# 1.net
KiCad netlist of a schematic drawn in EAGLE
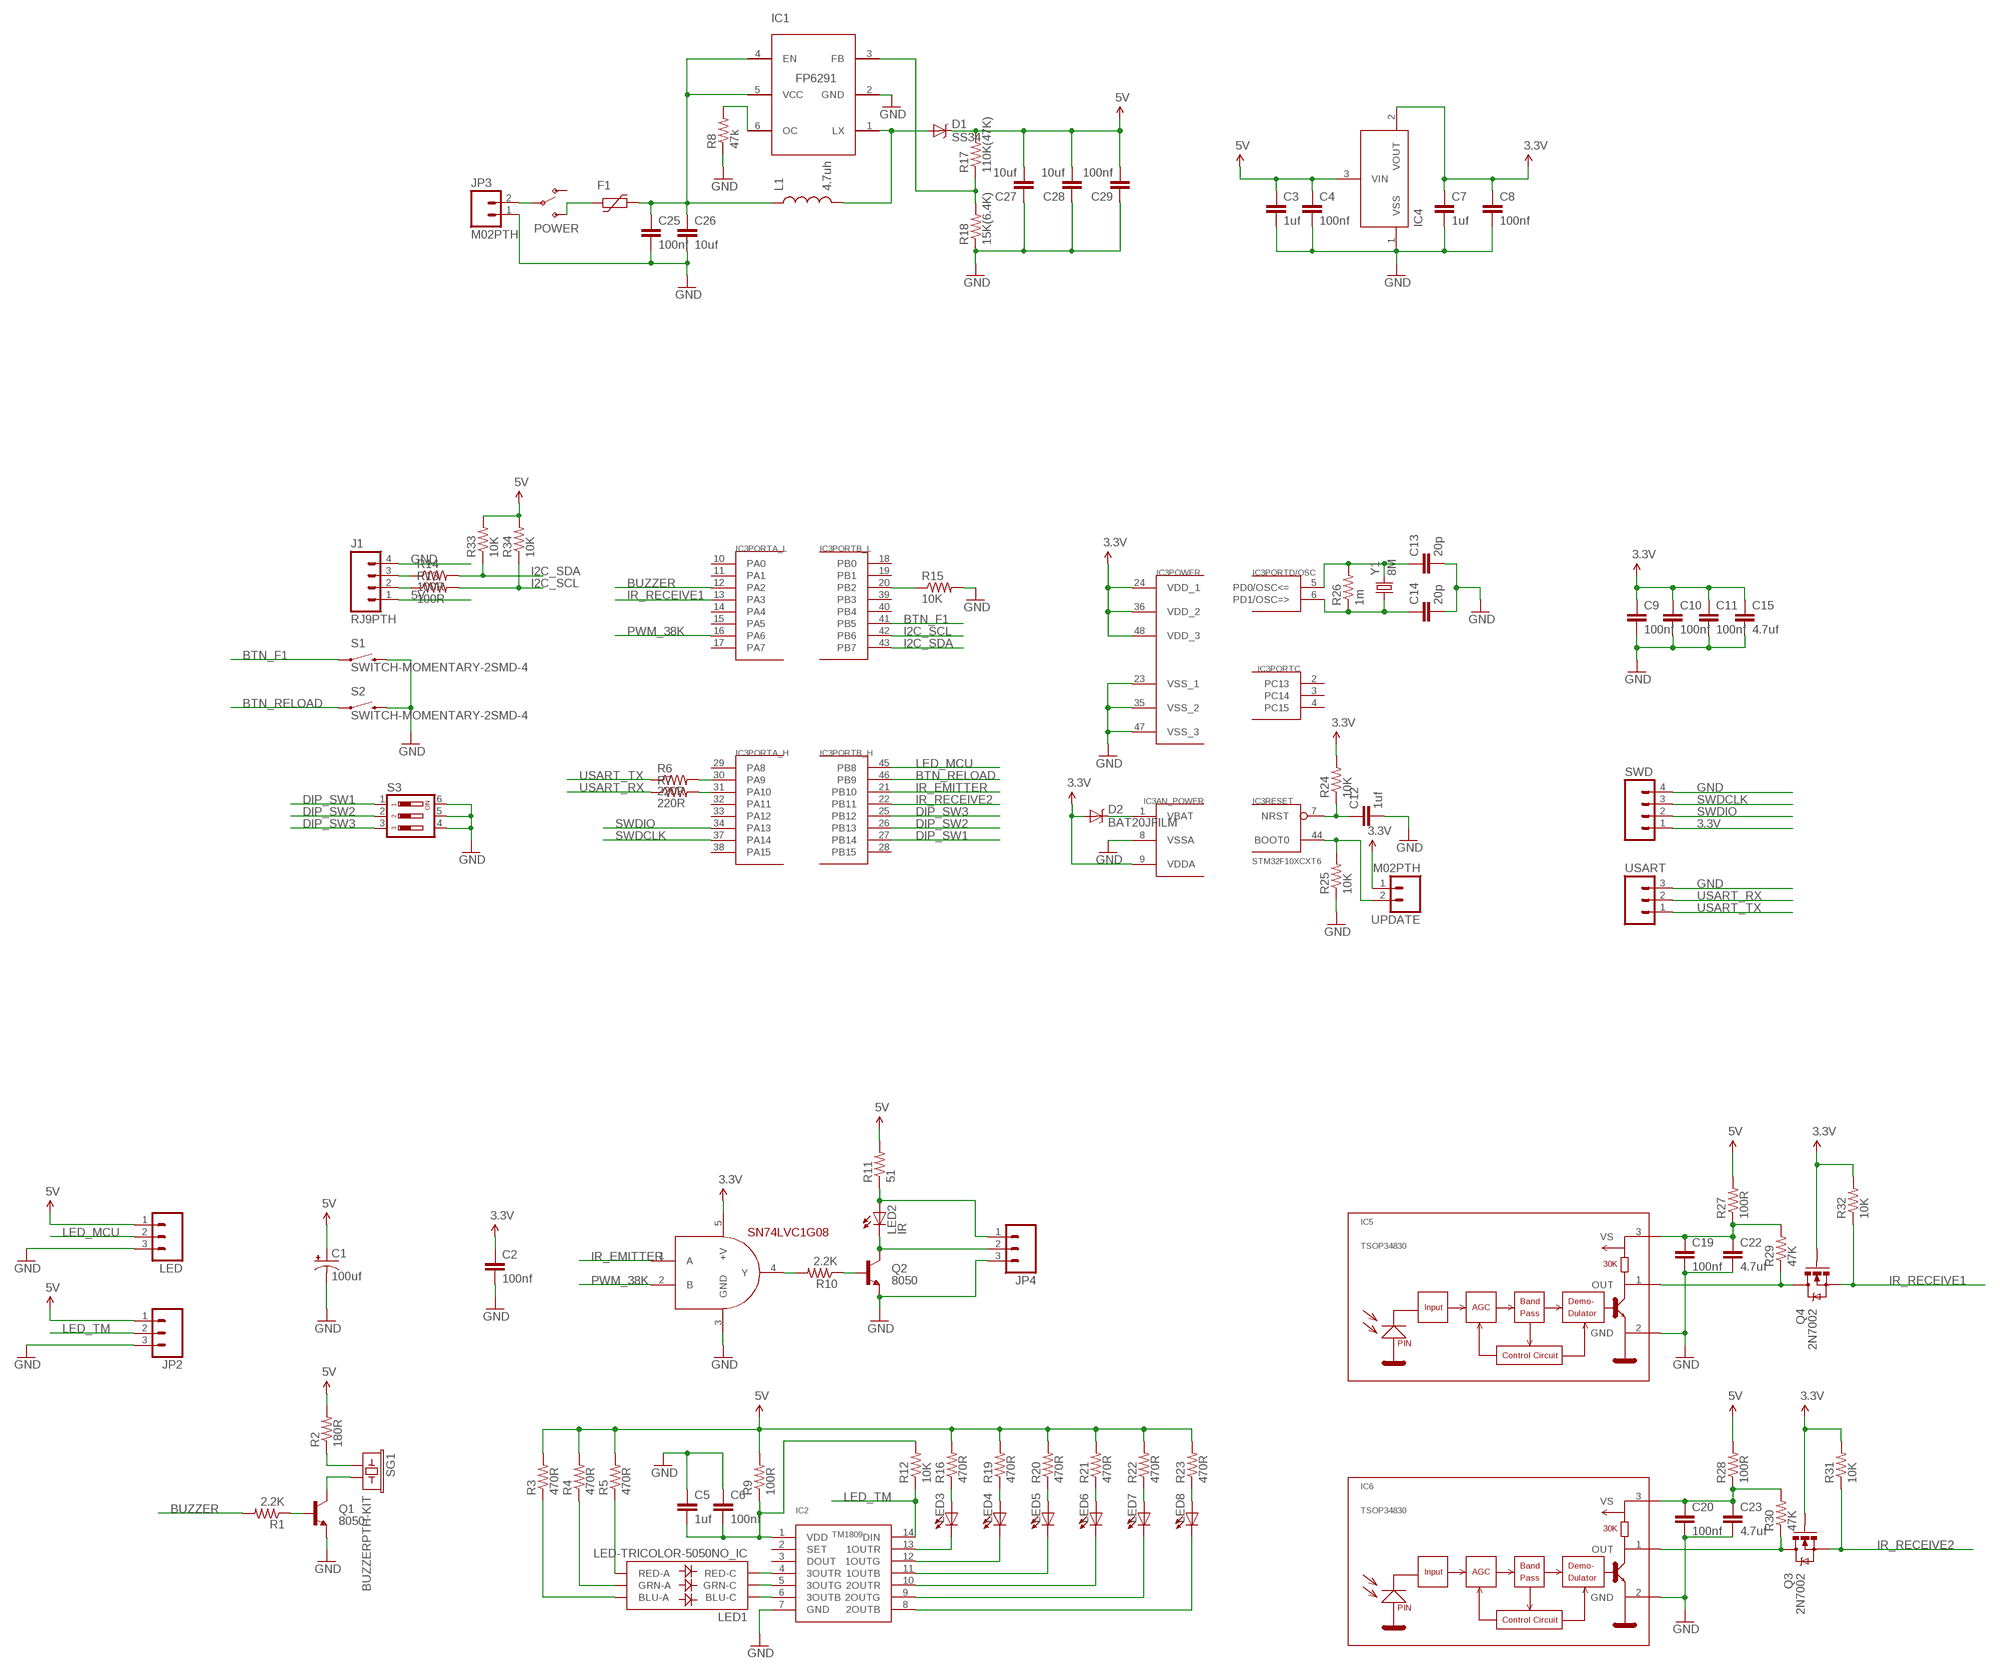
[diagram p0: schematic, sheet 1]

(export (version "E")
  (design (tool "Eeschema 10.0.6"))
  (components
    (comp (ref "C1")
      (value "100uf")
      (footprint "eagle-import:EIA6032")
      (libsource (lib "eagle-import") (part "CAP_POL6032"))
    )
    (comp (ref "C2")
      (value "100nf")
      (footprint "eagle-import:0603-CAP")
      (libsource (lib "eagle-import") (part "CAP0603-CAP"))
    )
    (comp (ref "C3")
      (value "1uf")
      (footprint "eagle-import:0603-CAP")
      (libsource (lib "eagle-import") (part "CAP0603-CAP"))
    )
    (comp (ref "C4")
      (value "100nf")
      (footprint "eagle-import:0603-CAP")
      (libsource (lib "eagle-import") (part "CAP0603-CAP"))
    )
    (comp (ref "C5")
      (value "1uf")
      (footprint "eagle-import:0603-CAP")
      (libsource (lib "eagle-import") (part "CAP0603-CAP"))
    )
    (comp (ref "C6")
      (value "100nf")
      (footprint "eagle-import:0603-CAP")
      (libsource (lib "eagle-import") (part "CAP0603-CAP"))
    )
    (comp (ref "C7")
      (value "1uf")
      (footprint "eagle-import:0603-CAP")
      (libsource (lib "eagle-import") (part "CAP0603-CAP"))
    )
    (comp (ref "C8")
      (value "100nf")
      (footprint "eagle-import:0603-CAP")
      (libsource (lib "eagle-import") (part "CAP0603-CAP"))
    )
    (comp (ref "C9")
      (value "100nf")
      (footprint "eagle-import:0603-CAP")
      (libsource (lib "eagle-import") (part "CAP0603-CAP"))
    )
    (comp (ref "C10")
      (value "100nf")
      (footprint "eagle-import:0603-CAP")
      (libsource (lib "eagle-import") (part "CAP0603-CAP"))
    )
    (comp (ref "C11")
      (value "100nf")
      (footprint "eagle-import:0603-CAP")
      (libsource (lib "eagle-import") (part "CAP0603-CAP"))
    )
    (comp (ref "C12")
      (value "1uf")
      (footprint "eagle-import:0603-CAP")
      (libsource (lib "eagle-import") (part "CAP0603-CAP"))
    )
    (comp (ref "C13")
      (value "20p")
      (footprint "eagle-import:0603-CAP")
      (libsource (lib "eagle-import") (part "CAP0603-CAP"))
    )
    (comp (ref "C14")
      (value "20p")
      (footprint "eagle-import:0603-CAP")
      (libsource (lib "eagle-import") (part "CAP0603-CAP"))
    )
    (comp (ref "C15")
      (value "4.7uf")
      (footprint "eagle-import:0603-CAP")
      (libsource (lib "eagle-import") (part "CAP0603-CAP"))
    )
    (comp (ref "C19")
      (value "100nf")
      (footprint "eagle-import:0603-CAP")
      (libsource (lib "eagle-import") (part "CAP0603-CAP"))
    )
    (comp (ref "C20")
      (value "100nf")
      (footprint "eagle-import:0603-CAP")
      (libsource (lib "eagle-import") (part "CAP0603-CAP"))
    )
    (comp (ref "C22")
      (value "4.7uf")
      (footprint "eagle-import:0603-CAP")
      (libsource (lib "eagle-import") (part "CAP0603-CAP"))
    )
    (comp (ref "C23")
      (value "4.7uf")
      (footprint "eagle-import:0603-CAP")
      (libsource (lib "eagle-import") (part "CAP0603-CAP"))
    )
    (comp (ref "C25")
      (value "100nf")
      (footprint "eagle-import:0603-CAP")
      (libsource (lib "eagle-import") (part "CAP0603-CAP"))
    )
    (comp (ref "C26")
      (value "10uf")
      (footprint "eagle-import:0603-CAP")
      (libsource (lib "eagle-import") (part "CAP0603-CAP"))
    )
    (comp (ref "C27")
      (value "10uf")
      (footprint "eagle-import:0603-CAP")
      (libsource (lib "eagle-import") (part "CAP0603-CAP"))
    )
    (comp (ref "C28")
      (value "10uf")
      (footprint "eagle-import:0603-CAP")
      (libsource (lib "eagle-import") (part "CAP0603-CAP"))
    )
    (comp (ref "C29")
      (value "100nf")
      (footprint "eagle-import:0603-CAP")
      (libsource (lib "eagle-import") (part "CAP0603-CAP"))
    )
    (comp (ref "D1")
      (value "SS34")
      (footprint "eagle-import:SMA-DIODE")
      (libsource (lib "eagle-import") (part "DIODE-SCHOTTKY_"))
    )
    (comp (ref "D2")
      (value "BAT20JFILM")
      (footprint "eagle-import:SOD-323")
      (libsource (lib "eagle-import") (part "BAT20JFILM"))
    )
    (comp (ref "F1")
      (value "PTC-FUSE")
      (footprint "eagle-import:R0805")
      (libsource (lib "eagle-import") (part "PTC-FUSE"))
    )
    (comp (ref "IC1")
      (value "FP6291")
      (footprint "eagle-import:SOT23-6")
      (libsource (lib "eagle-import") (part "FP6291"))
    )
    (comp (ref "IC2")
      (value "TM1809")
      (footprint "eagle-import:SOP-14")
      (libsource (lib "eagle-import") (part "TM1809"))
    )
    (comp (ref "IC3")
      (value "STM32F10XCXT6")
      (footprint "eagle-import:TQFP48")
      (libsource (lib "eagle-import") (part "STM32F10XCXT6"))
    )
    (comp (ref "IC4")
      (value "XC6206")
      (footprint "eagle-import:SOT23-3")
      (libsource (lib "eagle-import") (part "XC6206"))
    )
    (comp (ref "IC5")
      (value "TSOP34830")
      (footprint "eagle-import:TSOP348")
      (libsource (lib "eagle-import") (part "TSOP34830"))
    )
    (comp (ref "IC6")
      (value "TSOP34830")
      (footprint "eagle-import:TSOP348")
      (libsource (lib "eagle-import") (part "TSOP34830"))
    )
    (comp (ref "J1")
      (value "RJ9PTH")
      (footprint "eagle-import:RJ9")
      (libsource (lib "eagle-import") (part "RJ9PTH"))
    )
    (comp (ref "JP2")
      (value "M03PTH")
      (footprint "eagle-import:1X03")
      (libsource (lib "eagle-import") (part "M03PTH"))
    )
    (comp (ref "JP3")
      (value "M02PTH")
      (footprint "eagle-import:1X02")
      (libsource (lib "eagle-import") (part "M02PTH"))
    )
    (comp (ref "JP4")
      (value "M03PTH")
      (footprint "eagle-import:1X03")
      (libsource (lib "eagle-import") (part "M03PTH"))
    )
    (comp (ref "L1")
      (value "4.7uh")
      (footprint "eagle-import:CR75_V2")
      (libsource (lib "eagle-import") (part "INDUCTORCR75_V2"))
    )
    (comp (ref "LED")
      (value "M03PTH")
      (footprint "eagle-import:1X03")
      (libsource (lib "eagle-import") (part "M03PTH"))
    )
    (comp (ref "LED1")
      (value "LED-TRICOLOR-5050NO_IC")
      (footprint "eagle-import:LED-TRICOLOR-5050")
      (libsource (lib "eagle-import") (part "LED-TRICOLOR-5050NO_IC"))
    )
    (comp (ref "LED2")
      (value "IR")
      (footprint "eagle-import:LED5MM")
      (libsource (lib "eagle-import") (part "LED5MM"))
    )
    (comp (ref "LED3")
      (value "LED0805")
      (footprint "eagle-import:CHIPLED_0805")
      (libsource (lib "eagle-import") (part "LED0805"))
    )
    (comp (ref "LED4")
      (value "LED0805")
      (footprint "eagle-import:CHIPLED_0805")
      (libsource (lib "eagle-import") (part "LED0805"))
    )
    (comp (ref "LED5")
      (value "LED0805")
      (footprint "eagle-import:CHIPLED_0805")
      (libsource (lib "eagle-import") (part "LED0805"))
    )
    (comp (ref "LED6")
      (value "LED0805")
      (footprint "eagle-import:CHIPLED_0805")
      (libsource (lib "eagle-import") (part "LED0805"))
    )
    (comp (ref "LED7")
      (value "LED0805")
      (footprint "eagle-import:CHIPLED_0805")
      (libsource (lib "eagle-import") (part "LED0805"))
    )
    (comp (ref "LED8")
      (value "LED0805")
      (footprint "eagle-import:CHIPLED_0805")
      (libsource (lib "eagle-import") (part "LED0805"))
    )
    (comp (ref "POWER")
      (value "SWITCH-SPST3AM6")
      (footprint "eagle-import:SWITCH-SPDT-AM#6")
      (libsource (lib "eagle-import") (part "SWITCH-SPST3AM6"))
    )
    (comp (ref "Q1")
      (value "8050")
      (footprint "eagle-import:SOT23")
      (libsource (lib "eagle-import") (part "TRANSISTOR_NPNSOT23"))
    )
    (comp (ref "Q2")
      (value "8050")
      (footprint "eagle-import:SOT23")
      (libsource (lib "eagle-import") (part "TRANSISTOR_NPNSOT23"))
    )
    (comp (ref "Q3")
      (value "2N7002")
      (footprint "eagle-import:SOT23")
      (libsource (lib "eagle-import") (part "MOSFET-NCHANNELBSS138"))
    )
    (comp (ref "Q4")
      (value "2N7002")
      (footprint "eagle-import:SOT23")
      (libsource (lib "eagle-import") (part "MOSFET-NCHANNELBSS138"))
    )
    (comp (ref "R1")
      (value "2.2K")
      (footprint "eagle-import:0603-RES")
      (libsource (lib "eagle-import") (part "RESISTOR0603-RES"))
    )
    (comp (ref "R2")
      (value "180R")
      (footprint "eagle-import:0603-RES")
      (libsource (lib "eagle-import") (part "RESISTOR0603-RES"))
    )
    (comp (ref "R3")
      (value "470R")
      (footprint "eagle-import:0603-RES")
      (libsource (lib "eagle-import") (part "RESISTOR0603-RES"))
    )
    (comp (ref "R4")
      (value "470R")
      (footprint "eagle-import:0603-RES")
      (libsource (lib "eagle-import") (part "RESISTOR0603-RES"))
    )
    (comp (ref "R5")
      (value "470R")
      (footprint "eagle-import:0603-RES")
      (libsource (lib "eagle-import") (part "RESISTOR0603-RES"))
    )
    (comp (ref "R6")
      (value "220R")
      (footprint "eagle-import:0603-RES")
      (libsource (lib "eagle-import") (part "RESISTOR0603-RES"))
    )
    (comp (ref "R7")
      (value "220R")
      (footprint "eagle-import:0603-RES")
      (libsource (lib "eagle-import") (part "RESISTOR0603-RES"))
    )
    (comp (ref "R8")
      (value "47k")
      (footprint "eagle-import:0603-RES")
      (libsource (lib "eagle-import") (part "RESISTOR0603-RES"))
    )
    (comp (ref "R9")
      (value "100R")
      (footprint "eagle-import:0603-RES")
      (libsource (lib "eagle-import") (part "RESISTOR0603-RES"))
    )
    (comp (ref "R10")
      (value "2.2K")
      (footprint "eagle-import:0603-RES")
      (libsource (lib "eagle-import") (part "RESISTOR0603-RES"))
    )
    (comp (ref "R11")
      (value "51")
      (footprint "eagle-import:1206")
      (libsource (lib "eagle-import") (part "SparkFun-Resistors_RESISTOR1206"))
    )
    (comp (ref "R12")
      (value "10K")
      (footprint "eagle-import:0603-RES")
      (libsource (lib "eagle-import") (part "RESISTOR0603-RES"))
    )
    (comp (ref "R13")
      (value "100R")
      (footprint "eagle-import:0603-RES")
      (libsource (lib "eagle-import") (part "RESISTOR0603-RES"))
    )
    (comp (ref "R14")
      (value "100R")
      (footprint "eagle-import:0603-RES")
      (libsource (lib "eagle-import") (part "RESISTOR0603-RES"))
    )
    (comp (ref "R15")
      (value "10K")
      (footprint "eagle-import:0603-RES")
      (libsource (lib "eagle-import") (part "RESISTOR0603-RES"))
    )
    (comp (ref "R16")
      (value "470R")
      (footprint "eagle-import:0603-RES")
      (libsource (lib "eagle-import") (part "RESISTOR0603-RES"))
    )
    (comp (ref "R17")
      (value "110K(47K)")
      (footprint "eagle-import:0603-RES")
      (libsource (lib "eagle-import") (part "RESISTOR0603-RES"))
    )
    (comp (ref "R18")
      (value "15K(6.4K)")
      (footprint "eagle-import:0603-RES")
      (libsource (lib "eagle-import") (part "RESISTOR0603-RES"))
    )
    (comp (ref "R19")
      (value "470R")
      (footprint "eagle-import:0603-RES")
      (libsource (lib "eagle-import") (part "RESISTOR0603-RES"))
    )
    (comp (ref "R20")
      (value "470R")
      (footprint "eagle-import:0603-RES")
      (libsource (lib "eagle-import") (part "RESISTOR0603-RES"))
    )
    (comp (ref "R21")
      (value "470R")
      (footprint "eagle-import:0603-RES")
      (libsource (lib "eagle-import") (part "RESISTOR0603-RES"))
    )
    (comp (ref "R22")
      (value "470R")
      (footprint "eagle-import:0603-RES")
      (libsource (lib "eagle-import") (part "RESISTOR0603-RES"))
    )
    (comp (ref "R23")
      (value "470R")
      (footprint "eagle-import:0603-RES")
      (libsource (lib "eagle-import") (part "RESISTOR0603-RES"))
    )
    (comp (ref "R24")
      (value "10K")
      (footprint "eagle-import:0603-RES")
      (libsource (lib "eagle-import") (part "RESISTOR0603-RES"))
    )
    (comp (ref "R25")
      (value "10K")
      (footprint "eagle-import:0603-RES")
      (libsource (lib "eagle-import") (part "RESISTOR0603-RES"))
    )
    (comp (ref "R26")
      (value "1m")
      (footprint "eagle-import:0603-RES")
      (libsource (lib "eagle-import") (part "RESISTOR0603-RES"))
    )
    (comp (ref "R27")
      (value "100R")
      (footprint "eagle-import:0603-RES")
      (libsource (lib "eagle-import") (part "RESISTOR0603-RES"))
    )
    (comp (ref "R28")
      (value "100R")
      (footprint "eagle-import:0603-RES")
      (libsource (lib "eagle-import") (part "RESISTOR0603-RES"))
    )
    (comp (ref "R29")
      (value "47K")
      (footprint "eagle-import:0603-RES")
      (libsource (lib "eagle-import") (part "RESISTOR0603-RES"))
    )
    (comp (ref "R30")
      (value "47K")
      (footprint "eagle-import:0603-RES")
      (libsource (lib "eagle-import") (part "RESISTOR0603-RES"))
    )
    (comp (ref "R31")
      (value "10K")
      (footprint "eagle-import:0603-RES")
      (libsource (lib "eagle-import") (part "RESISTOR0603-RES"))
    )
    (comp (ref "R32")
      (value "10K")
      (footprint "eagle-import:0603-RES")
      (libsource (lib "eagle-import") (part "RESISTOR0603-RES"))
    )
    (comp (ref "R33")
      (value "10K")
      (footprint "eagle-import:0603-RES")
      (libsource (lib "eagle-import") (part "RESISTOR0603-RES"))
    )
    (comp (ref "R34")
      (value "10K")
      (footprint "eagle-import:0603-RES")
      (libsource (lib "eagle-import") (part "RESISTOR0603-RES"))
    )
    (comp (ref "S1")
      (value "SWITCH-MOMENTARY-2SMD-4")
      (footprint "eagle-import:TACTILE_SWITCH_TALL")
      (libsource (lib "eagle-import") (part "SWITCH-MOMENTARY-2SMD-4"))
    )
    (comp (ref "S2")
      (value "SWITCH-MOMENTARY-2SMD-4")
      (footprint "eagle-import:TACTILE_SWITCH_TALL")
      (libsource (lib "eagle-import") (part "SWITCH-MOMENTARY-2SMD-4"))
    )
    (comp (ref "S3")
      (value "DIP03YL")
      (footprint "eagle-import:DIP03YL")
      (libsource (lib "eagle-import") (part "DIP03YL"))
    )
    (comp (ref "SG1")
      (value "BUZZERPTH-KIT")
      (footprint "eagle-import:BUZZER-12MM-KIT")
      (libsource (lib "eagle-import") (part "BUZZERPTH-KIT"))
    )
    (comp (ref "SWD")
      (value "M04PTH")
      (footprint "eagle-import:1X04")
      (libsource (lib "eagle-import") (part "M04PTH"))
    )
    (comp (ref "U$1")
      (value "SN74LVC1G08")
      (footprint "eagle-import:SOT23-5")
      (libsource (lib "eagle-import") (part "SN74LVC1G08"))
    )
    (comp (ref "UPDATE")
      (value "M02PTH")
      (footprint "eagle-import:1X02")
      (libsource (lib "eagle-import") (part "M02PTH"))
    )
    (comp (ref "USART")
      (value "M03PTH")
      (footprint "eagle-import:1X03")
      (libsource (lib "eagle-import") (part "M03PTH"))
    )
    (comp (ref "Y1")
      (value "8M")
      (footprint "eagle-import:CRYSTAL-TXC-7A")
      (libsource (lib "eagle-import") (part "CRYSTALTXC-7A"))
    )
  )
  (nets
    (net (code "1") (name "/BTN_F1") (class "Default")
      (node (ref "IC3") (pin "41") (pinfunction "PB5_41") (pintype "bidirectional"))
      (node (ref "S1") (pin "A2") (pinfunction "1_A2") (pintype "passive"))
    )
    (net (code "2") (name "/BTN_RELOAD") (class "Default")
      (node (ref "IC3") (pin "46") (pinfunction "PB9_46") (pintype "bidirectional"))
      (node (ref "S2") (pin "A2") (pinfunction "1_A2") (pintype "passive"))
    )
    (net (code "3") (name "/BUZZER") (class "Default")
      (node (ref "IC3") (pin "12") (pinfunction "PA2_12") (pintype "bidirectional"))
      (node (ref "R1") (pin "2") (pinfunction "2_2") (pintype "passive"))
    )
    (net (code "4") (name "/DIP_SW1") (class "Default")
      (node (ref "IC3") (pin "27") (pinfunction "PB14_27") (pintype "bidirectional"))
      (node (ref "S3") (pin "1") (pinfunction "1_1") (pintype "passive"))
    )
    (net (code "5") (name "/DIP_SW2") (class "Default")
      (node (ref "IC3") (pin "26") (pinfunction "PB13_26") (pintype "bidirectional"))
      (node (ref "S3") (pin "2") (pinfunction "2_2") (pintype "passive"))
    )
    (net (code "6") (name "/DIP_SW3") (class "Default")
      (node (ref "IC3") (pin "25") (pinfunction "PB12_25") (pintype "bidirectional"))
      (node (ref "S3") (pin "3") (pinfunction "3_3") (pintype "passive"))
    )
    (net (code "7") (name "/I2C_SCL") (class "Default")
      (node (ref "IC3") (pin "42") (pinfunction "PB6_42") (pintype "bidirectional"))
      (node (ref "R13") (pin "2") (pinfunction "2_2") (pintype "passive"))
      (node (ref "R34") (pin "1") (pinfunction "1_1") (pintype "passive"))
    )
    (net (code "8") (name "/I2C_SDA") (class "Default")
      (node (ref "IC3") (pin "43") (pinfunction "PB7_43") (pintype "bidirectional"))
      (node (ref "R14") (pin "2") (pinfunction "2_2") (pintype "passive"))
      (node (ref "R33") (pin "1") (pinfunction "1_1") (pintype "passive"))
    )
    (net (code "9") (name "/IR_EMITTER") (class "Default")
      (node (ref "IC3") (pin "21") (pinfunction "PB10_21") (pintype "bidirectional"))
      (node (ref "U$1") (pin "1") (pinfunction "A_1") (pintype "bidirectional"))
    )
    (net (code "10") (name "/IR_RECEIVE1") (class "Default")
      (node (ref "IC3") (pin "13") (pinfunction "PA3_13") (pintype "bidirectional"))
      (node (ref "Q4") (pin "2") (pinfunction "S_2") (pintype "passive"))
      (node (ref "R32") (pin "1") (pinfunction "1_1") (pintype "passive"))
    )
    (net (code "11") (name "/IR_RECEIVE2") (class "Default")
      (node (ref "IC3") (pin "22") (pinfunction "PB11_22") (pintype "bidirectional"))
      (node (ref "Q3") (pin "2") (pinfunction "S_2") (pintype "passive"))
      (node (ref "R31") (pin "1") (pinfunction "1_1") (pintype "passive"))
    )
    (net (code "12") (name "/LED_MCU") (class "Default")
      (node (ref "IC3") (pin "45") (pinfunction "PB8_45") (pintype "bidirectional"))
      (node (ref "LED") (pin "2") (pinfunction "2_2") (pintype "passive"))
    )
    (net (code "13") (name "/LED_TM") (class "Default")
      (node (ref "IC2") (pin "14") (pinfunction "DIN_14") (pintype "input"))
      (node (ref "JP2") (pin "2") (pinfunction "2_2") (pintype "passive"))
      (node (ref "R12") (pin "1") (pinfunction "1_1") (pintype "passive"))
    )
    (net (code "14") (name "/PWM_38K") (class "Default")
      (node (ref "IC3") (pin "16") (pinfunction "PA6_16") (pintype "bidirectional"))
      (node (ref "U$1") (pin "2") (pinfunction "B_2") (pintype "bidirectional"))
    )
    (net (code "15") (name "/SWDCLK") (class "Default")
      (node (ref "IC3") (pin "37") (pinfunction "PA14_37") (pintype "bidirectional"))
      (node (ref "SWD") (pin "3") (pinfunction "3_3") (pintype "passive"))
    )
    (net (code "16") (name "/SWDIO") (class "Default")
      (node (ref "IC3") (pin "34") (pinfunction "PA13_34") (pintype "bidirectional"))
      (node (ref "SWD") (pin "2") (pinfunction "2_2") (pintype "passive"))
    )
    (net (code "17") (name "/USART_RX") (class "Default")
      (node (ref "R7") (pin "1") (pinfunction "1_1") (pintype "passive"))
      (node (ref "USART") (pin "2") (pinfunction "2_2") (pintype "passive"))
    )
    (net (code "18") (name "/USART_TX") (class "Default")
      (node (ref "R6") (pin "1") (pinfunction "1_1") (pintype "passive"))
      (node (ref "USART") (pin "1") (pinfunction "1_1") (pintype "passive"))
    )
    (net (code "19") (name "3.3V") (class "Default")
      (node (ref "C10") (pin "1") (pinfunction "1_1") (pintype "passive"))
      (node (ref "C11") (pin "1") (pinfunction "1_1") (pintype "passive"))
      (node (ref "C15") (pin "1") (pinfunction "1_1") (pintype "passive"))
      (node (ref "C2") (pin "1") (pinfunction "1_1") (pintype "passive"))
      (node (ref "C7") (pin "1") (pinfunction "1_1") (pintype "passive"))
      (node (ref "C8") (pin "1") (pinfunction "1_1") (pintype "passive"))
      (node (ref "C9") (pin "1") (pinfunction "1_1") (pintype "passive"))
      (node (ref "D2") (pin "2") (pinfunction "A_2") (pintype "passive"))
      (node (ref "IC3") (pin "24") (pinfunction "VDD_1_24") (pintype "power_in"))
      (node (ref "IC3") (pin "36") (pinfunction "VDD_2_36") (pintype "power_in"))
      (node (ref "IC3") (pin "48") (pinfunction "VDD_3_48") (pintype "power_in"))
      (node (ref "IC3") (pin "9") (pinfunction "VDDA_9") (pintype "power_in"))
      (node (ref "IC4") (pin "2") (pinfunction "VOUT_2") (pintype "power_in"))
      (node (ref "Q3") (pin "1") (pinfunction "G_1") (pintype "passive"))
      (node (ref "Q4") (pin "1") (pinfunction "G_1") (pintype "passive"))
      (node (ref "R24") (pin "2") (pinfunction "2_2") (pintype "passive"))
      (node (ref "R31") (pin "2") (pinfunction "2_2") (pintype "passive"))
      (node (ref "R32") (pin "2") (pinfunction "2_2") (pintype "passive"))
      (node (ref "SWD") (pin "1") (pinfunction "1_1") (pintype "passive"))
      (node (ref "U$1") (pin "5") (pinfunction "+V_5") (pintype "bidirectional"))
      (node (ref "UPDATE") (pin "1") (pinfunction "1_1") (pintype "passive"))
    )
    (net (code "20") (name "5V") (class "Default")
      (node (ref "C1") (pin "P$1") (pinfunction "+_P$1") (pintype "passive"))
      (node (ref "C27") (pin "2") (pinfunction "2_2") (pintype "passive"))
      (node (ref "C28") (pin "2") (pinfunction "2_2") (pintype "passive"))
      (node (ref "C29") (pin "2") (pinfunction "2_2") (pintype "passive"))
      (node (ref "C3") (pin "1") (pinfunction "1_1") (pintype "passive"))
      (node (ref "C4") (pin "1") (pinfunction "1_1") (pintype "passive"))
      (node (ref "D1") (pin "C") (pinfunction "C_C") (pintype "passive"))
      (node (ref "IC4") (pin "3") (pinfunction "VIN_3") (pintype "power_in"))
      (node (ref "J1") (pin "1") (pinfunction "1_1") (pintype "passive"))
      (node (ref "JP2") (pin "1") (pinfunction "1_1") (pintype "passive"))
      (node (ref "LED") (pin "1") (pinfunction "1_1") (pintype "passive"))
      (node (ref "R11") (pin "2") (pinfunction "2_2") (pintype "passive"))
      (node (ref "R16") (pin "2") (pinfunction "2_2") (pintype "passive"))
      (node (ref "R17") (pin "2") (pinfunction "2_2") (pintype "passive"))
      (node (ref "R19") (pin "2") (pinfunction "2_2") (pintype "passive"))
      (node (ref "R2") (pin "2") (pinfunction "2_2") (pintype "passive"))
      (node (ref "R20") (pin "2") (pinfunction "2_2") (pintype "passive"))
      (node (ref "R21") (pin "2") (pinfunction "2_2") (pintype "passive"))
      (node (ref "R22") (pin "2") (pinfunction "2_2") (pintype "passive"))
      (node (ref "R23") (pin "2") (pinfunction "2_2") (pintype "passive"))
      (node (ref "R27") (pin "2") (pinfunction "2_2") (pintype "passive"))
      (node (ref "R28") (pin "2") (pinfunction "2_2") (pintype "passive"))
      (node (ref "R3") (pin "2") (pinfunction "2_2") (pintype "passive"))
      (node (ref "R33") (pin "2") (pinfunction "2_2") (pintype "passive"))
      (node (ref "R34") (pin "2") (pinfunction "2_2") (pintype "passive"))
      (node (ref "R4") (pin "2") (pinfunction "2_2") (pintype "passive"))
      (node (ref "R5") (pin "2") (pinfunction "2_2") (pintype "passive"))
      (node (ref "R9") (pin "2") (pinfunction "2_2") (pintype "passive"))
    )
    (net (code "21") (name "GND") (class "Default")
      (node (ref "C1") (pin "P$2") (pinfunction "-_P$2") (pintype "passive"))
      (node (ref "C10") (pin "2") (pinfunction "2_2") (pintype "passive"))
      (node (ref "C11") (pin "2") (pinfunction "2_2") (pintype "passive"))
      (node (ref "C12") (pin "2") (pinfunction "2_2") (pintype "passive"))
      (node (ref "C13") (pin "2") (pinfunction "2_2") (pintype "passive"))
      (node (ref "C14") (pin "2") (pinfunction "2_2") (pintype "passive"))
      (node (ref "C15") (pin "2") (pinfunction "2_2") (pintype "passive"))
      (node (ref "C19") (pin "2") (pinfunction "2_2") (pintype "passive"))
      (node (ref "C2") (pin "2") (pinfunction "2_2") (pintype "passive"))
      (node (ref "C20") (pin "2") (pinfunction "2_2") (pintype "passive"))
      (node (ref "C22") (pin "2") (pinfunction "2_2") (pintype "passive"))
      (node (ref "C23") (pin "2") (pinfunction "2_2") (pintype "passive"))
      (node (ref "C25") (pin "2") (pinfunction "2_2") (pintype "passive"))
      (node (ref "C26") (pin "2") (pinfunction "2_2") (pintype "passive"))
      (node (ref "C27") (pin "1") (pinfunction "1_1") (pintype "passive"))
      (node (ref "C28") (pin "1") (pinfunction "1_1") (pintype "passive"))
      (node (ref "C29") (pin "1") (pinfunction "1_1") (pintype "passive"))
      (node (ref "C3") (pin "2") (pinfunction "2_2") (pintype "passive"))
      (node (ref "C4") (pin "2") (pinfunction "2_2") (pintype "passive"))
      (node (ref "C5") (pin "1") (pinfunction "1_1") (pintype "passive"))
      (node (ref "C6") (pin "1") (pinfunction "1_1") (pintype "passive"))
      (node (ref "C7") (pin "2") (pinfunction "2_2") (pintype "passive"))
      (node (ref "C8") (pin "2") (pinfunction "2_2") (pintype "passive"))
      (node (ref "C9") (pin "2") (pinfunction "2_2") (pintype "passive"))
      (node (ref "IC1") (pin "2") (pinfunction "GND_2") (pintype "power_in"))
      (node (ref "IC2") (pin "7") (pinfunction "GND_7") (pintype "power_in"))
      (node (ref "IC3") (pin "23") (pinfunction "VSS_1_23") (pintype "power_in"))
      (node (ref "IC3") (pin "35") (pinfunction "VSS_2_35") (pintype "power_in"))
      (node (ref "IC3") (pin "47") (pinfunction "VSS_3_47") (pintype "power_in"))
      (node (ref "IC3") (pin "8") (pinfunction "VSSA_8") (pintype "power_in"))
      (node (ref "IC4") (pin "1") (pinfunction "VSS_1") (pintype "power_in"))
      (node (ref "IC5") (pin "2") (pinfunction "GND_2") (pintype "power_in"))
      (node (ref "IC6") (pin "2") (pinfunction "GND_2") (pintype "power_in"))
      (node (ref "J1") (pin "4") (pinfunction "4_4") (pintype "passive"))
      (node (ref "JP2") (pin "3") (pinfunction "3_3") (pintype "passive"))
      (node (ref "JP3") (pin "1") (pinfunction "1_1") (pintype "passive"))
      (node (ref "JP4") (pin "3") (pinfunction "3_3") (pintype "passive"))
      (node (ref "LED") (pin "3") (pinfunction "3_3") (pintype "passive"))
      (node (ref "Q1") (pin "2") (pinfunction "E_2") (pintype "passive"))
      (node (ref "Q2") (pin "2") (pinfunction "E_2") (pintype "passive"))
      (node (ref "R15") (pin "2") (pinfunction "2_2") (pintype "passive"))
      (node (ref "R18") (pin "1") (pinfunction "1_1") (pintype "passive"))
      (node (ref "R25") (pin "1") (pinfunction "1_1") (pintype "passive"))
      (node (ref "R8") (pin "1") (pinfunction "1_1") (pintype "passive"))
      (node (ref "S1") (pin "B2") (pinfunction "2_B2") (pintype "passive"))
      (node (ref "S2") (pin "B2") (pinfunction "2_B2") (pintype "passive"))
      (node (ref "S3") (pin "4") (pinfunction "4_4") (pintype "passive"))
      (node (ref "S3") (pin "5") (pinfunction "5_5") (pintype "passive"))
      (node (ref "S3") (pin "6") (pinfunction "6_6") (pintype "passive"))
      (node (ref "SWD") (pin "4") (pinfunction "4_4") (pintype "passive"))
      (node (ref "U$1") (pin "3") (pinfunction "GND_3") (pintype "bidirectional"))
      (node (ref "USART") (pin "3") (pinfunction "3_3") (pintype "passive"))
    )
    (net (code "22") (name "Net-(D2-C)") (class "Default")
      (node (ref "D2") (pin "1") (pinfunction "C_1") (pintype "passive"))
      (node (ref "IC3") (pin "1") (pinfunction "VBAT_1") (pintype "power_in"))
    )
    (net (code "23") (name "Net-(IC1-EN)") (class "Default")
      (node (ref "C25") (pin "1") (pinfunction "1_1") (pintype "passive"))
      (node (ref "C26") (pin "1") (pinfunction "1_1") (pintype "passive"))
      (node (ref "F1") (pin "2") (pinfunction "2_2") (pintype "passive"))
      (node (ref "IC1") (pin "4") (pinfunction "EN_4") (pintype "bidirectional"))
      (node (ref "IC1") (pin "5") (pinfunction "VCC_5") (pintype "power_in"))
      (node (ref "L1") (pin "P$1") (pinfunction "1_P$1") (pintype "passive"))
    )
    (net (code "24") (name "Net-(IC1-FB)") (class "Default")
      (node (ref "IC1") (pin "3") (pinfunction "FB_3") (pintype "bidirectional"))
      (node (ref "R17") (pin "1") (pinfunction "1_1") (pintype "passive"))
      (node (ref "R18") (pin "2") (pinfunction "2_2") (pintype "passive"))
    )
    (net (code "25") (name "Net-(IC1-LX)") (class "Default")
      (node (ref "D1") (pin "A") (pinfunction "A_A") (pintype "passive"))
      (node (ref "IC1") (pin "1") (pinfunction "LX_1") (pintype "bidirectional"))
      (node (ref "L1") (pin "P$2") (pinfunction "2_P$2") (pintype "passive"))
    )
    (net (code "26") (name "Net-(IC1-OC)") (class "Default")
      (node (ref "IC1") (pin "6") (pinfunction "OC_6") (pintype "open_collector"))
      (node (ref "R8") (pin "2") (pinfunction "2_2") (pintype "passive"))
    )
    (net (code "27") (name "Net-(IC2-1OUTB)") (class "Default")
      (node (ref "IC2") (pin "11") (pinfunction "1OUTB_11") (pintype "output"))
      (node (ref "LED5") (pin "C") (pinfunction "C_C") (pintype "passive"))
    )
    (net (code "28") (name "Net-(IC2-1OUTG)") (class "Default")
      (node (ref "IC2") (pin "12") (pinfunction "1OUTG_12") (pintype "output"))
      (node (ref "LED4") (pin "C") (pinfunction "C_C") (pintype "passive"))
    )
    (net (code "29") (name "Net-(IC2-1OUTR)") (class "Default")
      (node (ref "IC2") (pin "13") (pinfunction "1OUTR_13") (pintype "output"))
      (node (ref "LED3") (pin "C") (pinfunction "C_C") (pintype "passive"))
    )
    (net (code "30") (name "Net-(IC2-2OUTB)") (class "Default")
      (node (ref "IC2") (pin "8") (pinfunction "2OUTB_8") (pintype "output"))
      (node (ref "LED8") (pin "C") (pinfunction "C_C") (pintype "passive"))
    )
    (net (code "31") (name "Net-(IC2-2OUTG)") (class "Default")
      (node (ref "IC2") (pin "9") (pinfunction "2OUTG_9") (pintype "output"))
      (node (ref "LED7") (pin "C") (pinfunction "C_C") (pintype "passive"))
    )
    (net (code "32") (name "Net-(IC2-2OUTR)") (class "Default")
      (node (ref "IC2") (pin "10") (pinfunction "2OUTR_10") (pintype "output"))
      (node (ref "LED6") (pin "C") (pinfunction "C_C") (pintype "passive"))
    )
    (net (code "33") (name "Net-(IC2-3OUTB)") (class "Default")
      (node (ref "IC2") (pin "6") (pinfunction "3OUTB_6") (pintype "output"))
      (node (ref "LED1") (pin "4") (pinfunction "BLU-C_4") (pintype "bidirectional"))
    )
    (net (code "34") (name "Net-(IC2-3OUTG)") (class "Default")
      (node (ref "IC2") (pin "5") (pinfunction "3OUTG_5") (pintype "output"))
      (node (ref "LED1") (pin "6") (pinfunction "GRN-C_6") (pintype "bidirectional"))
    )
    (net (code "35") (name "Net-(IC2-3OUTR)") (class "Default")
      (node (ref "IC2") (pin "4") (pinfunction "3OUTR_4") (pintype "output"))
      (node (ref "LED1") (pin "5") (pinfunction "RED-C_5") (pintype "bidirectional"))
    )
    (net (code "36") (name "Net-(IC2-VDD)") (class "Default")
      (node (ref "C5") (pin "2") (pinfunction "2_2") (pintype "passive"))
      (node (ref "C6") (pin "2") (pinfunction "2_2") (pintype "passive"))
      (node (ref "IC2") (pin "1") (pinfunction "VDD_1") (pintype "power_in"))
      (node (ref "R12") (pin "2") (pinfunction "2_2") (pintype "passive"))
      (node (ref "R9") (pin "1") (pinfunction "1_1") (pintype "passive"))
    )
    (net (code "37") (name "Net-(IC3B-PA9)") (class "Default")
      (node (ref "IC3") (pin "30") (pinfunction "PA9_30") (pintype "bidirectional"))
      (node (ref "R6") (pin "2") (pinfunction "2_2") (pintype "passive"))
    )
    (net (code "38") (name "Net-(IC3B-PA10)") (class "Default")
      (node (ref "IC3") (pin "31") (pinfunction "PA10_31") (pintype "bidirectional"))
      (node (ref "R7") (pin "2") (pinfunction "2_2") (pintype "passive"))
    )
    (net (code "39") (name "Net-(IC3E-PB2)") (class "Default")
      (node (ref "IC3") (pin "20") (pinfunction "PB2_20") (pintype "bidirectional"))
      (node (ref "R15") (pin "1") (pinfunction "1_1") (pintype "passive"))
    )
    (net (code "40") (name "Net-(IC3G-PD0{slash}OSC<=)") (class "Default")
      (node (ref "C13") (pin "1") (pinfunction "1_1") (pintype "passive"))
      (node (ref "IC3") (pin "5") (pinfunction "PD0/OSC<=_5") (pintype "bidirectional"))
      (node (ref "R26") (pin "2") (pinfunction "2_2") (pintype "passive"))
      (node (ref "Y1") (pin "P$2") (pinfunction "2_P$2") (pintype "passive"))
    )
    (net (code "41") (name "Net-(IC3G-PD1{slash}OSC=>)") (class "Default")
      (node (ref "C14") (pin "1") (pinfunction "1_1") (pintype "passive"))
      (node (ref "IC3") (pin "6") (pinfunction "PD1/OSC=>_6") (pintype "bidirectional"))
      (node (ref "R26") (pin "1") (pinfunction "1_1") (pintype "passive"))
      (node (ref "Y1") (pin "P$1") (pinfunction "1_P$1") (pintype "passive"))
    )
    (net (code "42") (name "Net-(IC3I-BOOT0)") (class "Default")
      (node (ref "IC3") (pin "44") (pinfunction "BOOT0_44") (pintype "input"))
      (node (ref "R25") (pin "2") (pinfunction "2_2") (pintype "passive"))
      (node (ref "UPDATE") (pin "2") (pinfunction "2_2") (pintype "passive"))
    )
    (net (code "43") (name "Net-(IC3I-NRST)") (class "Default")
      (node (ref "C12") (pin "1") (pinfunction "1_1") (pintype "passive"))
      (node (ref "IC3") (pin "7") (pinfunction "NRST_7") (pintype "input"))
      (node (ref "R24") (pin "1") (pinfunction "1_1") (pintype "passive"))
    )
    (net (code "44") (name "Net-(IC5-OUT)") (class "Default")
      (node (ref "IC5") (pin "1") (pinfunction "OUT_1") (pintype "output"))
      (node (ref "Q4") (pin "3") (pinfunction "D_3") (pintype "passive"))
      (node (ref "R29") (pin "1") (pinfunction "1_1") (pintype "passive"))
    )
    (net (code "45") (name "Net-(IC5-VS)") (class "Default")
      (node (ref "C19") (pin "1") (pinfunction "1_1") (pintype "passive"))
      (node (ref "C22") (pin "1") (pinfunction "1_1") (pintype "passive"))
      (node (ref "IC5") (pin "3") (pinfunction "VS_3") (pintype "power_in"))
      (node (ref "R27") (pin "1") (pinfunction "1_1") (pintype "passive"))
      (node (ref "R29") (pin "2") (pinfunction "2_2") (pintype "passive"))
    )
    (net (code "46") (name "Net-(IC6-OUT)") (class "Default")
      (node (ref "IC6") (pin "1") (pinfunction "OUT_1") (pintype "output"))
      (node (ref "Q3") (pin "3") (pinfunction "D_3") (pintype "passive"))
      (node (ref "R30") (pin "1") (pinfunction "1_1") (pintype "passive"))
    )
    (net (code "47") (name "Net-(IC6-VS)") (class "Default")
      (node (ref "C20") (pin "1") (pinfunction "1_1") (pintype "passive"))
      (node (ref "C23") (pin "1") (pinfunction "1_1") (pintype "passive"))
      (node (ref "IC6") (pin "3") (pinfunction "VS_3") (pintype "power_in"))
      (node (ref "R28") (pin "1") (pinfunction "1_1") (pintype "passive"))
      (node (ref "R30") (pin "2") (pinfunction "2_2") (pintype "passive"))
    )
    (net (code "48") (name "Net-(J1-Pad2)") (class "Default")
      (node (ref "J1") (pin "2") (pinfunction "2_2") (pintype "passive"))
      (node (ref "R13") (pin "1") (pinfunction "1_1") (pintype "passive"))
    )
    (net (code "49") (name "Net-(J1-Pad3)") (class "Default")
      (node (ref "J1") (pin "3") (pinfunction "3_3") (pintype "passive"))
      (node (ref "R14") (pin "1") (pinfunction "1_1") (pintype "passive"))
    )
    (net (code "50") (name "Net-(JP4-Pad1)") (class "Default")
      (node (ref "JP4") (pin "1") (pinfunction "1_1") (pintype "passive"))
      (node (ref "LED2") (pin "A") (pinfunction "A_A") (pintype "passive"))
      (node (ref "R11") (pin "1") (pinfunction "1_1") (pintype "passive"))
    )
    (net (code "51") (name "Net-(LED1-BLU-A)") (class "Default")
      (node (ref "LED1") (pin "3") (pinfunction "BLU-A_3") (pintype "bidirectional"))
      (node (ref "R3") (pin "1") (pinfunction "1_1") (pintype "passive"))
    )
    (net (code "52") (name "Net-(LED1-GRN-A)") (class "Default")
      (node (ref "LED1") (pin "1") (pinfunction "GRN-A_1") (pintype "bidirectional"))
      (node (ref "R4") (pin "1") (pinfunction "1_1") (pintype "passive"))
    )
    (net (code "53") (name "Net-(LED1-RED-A)") (class "Default")
      (node (ref "LED1") (pin "2") (pinfunction "RED-A_2") (pintype "bidirectional"))
      (node (ref "R5") (pin "1") (pinfunction "1_1") (pintype "passive"))
    )
    (net (code "54") (name "Net-(LED2-C)") (class "Default")
      (node (ref "JP4") (pin "2") (pinfunction "2_2") (pintype "passive"))
      (node (ref "LED2") (pin "K") (pinfunction "C_K") (pintype "passive"))
      (node (ref "Q2") (pin "3") (pinfunction "C_3") (pintype "passive"))
    )
    (net (code "55") (name "Net-(LED3-PadA)") (class "Default")
      (node (ref "LED3") (pin "A") (pinfunction "A_A") (pintype "passive"))
      (node (ref "R16") (pin "1") (pinfunction "1_1") (pintype "passive"))
    )
    (net (code "56") (name "Net-(LED4-PadA)") (class "Default")
      (node (ref "LED4") (pin "A") (pinfunction "A_A") (pintype "passive"))
      (node (ref "R19") (pin "1") (pinfunction "1_1") (pintype "passive"))
    )
    (net (code "57") (name "Net-(LED5-PadA)") (class "Default")
      (node (ref "LED5") (pin "A") (pinfunction "A_A") (pintype "passive"))
      (node (ref "R20") (pin "1") (pinfunction "1_1") (pintype "passive"))
    )
    (net (code "58") (name "Net-(LED6-PadA)") (class "Default")
      (node (ref "LED6") (pin "A") (pinfunction "A_A") (pintype "passive"))
      (node (ref "R21") (pin "1") (pinfunction "1_1") (pintype "passive"))
    )
    (net (code "59") (name "Net-(LED7-PadA)") (class "Default")
      (node (ref "LED7") (pin "A") (pinfunction "A_A") (pintype "passive"))
      (node (ref "R22") (pin "1") (pinfunction "1_1") (pintype "passive"))
    )
    (net (code "60") (name "Net-(LED8-PadA)") (class "Default")
      (node (ref "LED8") (pin "A") (pinfunction "A_A") (pintype "passive"))
      (node (ref "R23") (pin "1") (pinfunction "1_1") (pintype "passive"))
    )
    (net (code "61") (name "Net-(POWER-P)") (class "Default")
      (node (ref "JP3") (pin "2") (pinfunction "2_2") (pintype "passive"))
      (node (ref "POWER") (pin "2") (pinfunction "P_2") (pintype "passive"))
    )
    (net (code "62") (name "Net-(POWER-S)") (class "Default")
      (node (ref "F1") (pin "1") (pinfunction "1_1") (pintype "passive"))
      (node (ref "POWER") (pin "3") (pinfunction "S_3") (pintype "passive"))
    )
    (net (code "63") (name "Net-(Q1-B)") (class "Default")
      (node (ref "Q1") (pin "1") (pinfunction "B_1") (pintype "passive"))
      (node (ref "R1") (pin "1") (pinfunction "1_1") (pintype "passive"))
    )
    (net (code "64") (name "Net-(Q1-C)") (class "Default")
      (node (ref "Q1") (pin "3") (pinfunction "C_3") (pintype "passive"))
      (node (ref "SG1") (pin "-") (pinfunction "2_-") (pintype "passive"))
    )
    (net (code "65") (name "Net-(Q2-B)") (class "Default")
      (node (ref "Q2") (pin "1") (pinfunction "B_1") (pintype "passive"))
      (node (ref "R10") (pin "1") (pinfunction "1_1") (pintype "passive"))
    )
    (net (code "66") (name "Net-(SG1-1)") (class "Default")
      (node (ref "R2") (pin "1") (pinfunction "1_1") (pintype "passive"))
      (node (ref "SG1") (pin "+") (pinfunction "1_+") (pintype "passive"))
    )
    (net (code "67") (name "Net-(U$1-Y)") (class "Default")
      (node (ref "R10") (pin "2") (pinfunction "2_2") (pintype "passive"))
      (node (ref "U$1") (pin "4") (pinfunction "Y_4") (pintype "bidirectional"))
    )
    (net (code "68") (name "unconnected-(IC2-DOUT-Pad3)") (class "Default")
      (node (ref "IC2") (pin "3") (pinfunction "DOUT_3") (pintype "output"))
    )
    (net (code "69") (name "unconnected-(IC2-SET-Pad2)") (class "Default")
      (node (ref "IC2") (pin "2") (pinfunction "SET_2") (pintype "input"))
    )
    (net (code "70") (name "unconnected-(IC3B-PA8-Pad29)") (class "Default")
      (node (ref "IC3") (pin "29") (pinfunction "PA8_29") (pintype "bidirectional"))
    )
    (net (code "71") (name "unconnected-(IC3B-PA11-Pad32)") (class "Default")
      (node (ref "IC3") (pin "32") (pinfunction "PA11_32") (pintype "bidirectional"))
    )
    (net (code "72") (name "unconnected-(IC3B-PA12-Pad33)") (class "Default")
      (node (ref "IC3") (pin "33") (pinfunction "PA12_33") (pintype "bidirectional"))
    )
    (net (code "73") (name "unconnected-(IC3B-PA15-Pad38)") (class "Default")
      (node (ref "IC3") (pin "38") (pinfunction "PA15_38") (pintype "bidirectional"))
    )
    (net (code "74") (name "unconnected-(IC3C-PA0-Pad10)") (class "Default")
      (node (ref "IC3") (pin "10") (pinfunction "PA0_10") (pintype "bidirectional"))
    )
    (net (code "75") (name "unconnected-(IC3C-PA1-Pad11)") (class "Default")
      (node (ref "IC3") (pin "11") (pinfunction "PA1_11") (pintype "bidirectional"))
    )
    (net (code "76") (name "unconnected-(IC3C-PA4-Pad14)") (class "Default")
      (node (ref "IC3") (pin "14") (pinfunction "PA4_14") (pintype "bidirectional"))
    )
    (net (code "77") (name "unconnected-(IC3C-PA5-Pad15)") (class "Default")
      (node (ref "IC3") (pin "15") (pinfunction "PA5_15") (pintype "bidirectional"))
    )
    (net (code "78") (name "unconnected-(IC3C-PA7-Pad17)") (class "Default")
      (node (ref "IC3") (pin "17") (pinfunction "PA7_17") (pintype "bidirectional"))
    )
    (net (code "79") (name "unconnected-(IC3D-PB15-Pad28)") (class "Default")
      (node (ref "IC3") (pin "28") (pinfunction "PB15_28") (pintype "bidirectional"))
    )
    (net (code "80") (name "unconnected-(IC3E-PB0-Pad18)") (class "Default")
      (node (ref "IC3") (pin "18") (pinfunction "PB0_18") (pintype "bidirectional"))
    )
    (net (code "81") (name "unconnected-(IC3E-PB1-Pad19)") (class "Default")
      (node (ref "IC3") (pin "19") (pinfunction "PB1_19") (pintype "bidirectional"))
    )
    (net (code "82") (name "unconnected-(IC3E-PB3-Pad39)") (class "Default")
      (node (ref "IC3") (pin "39") (pinfunction "PB3_39") (pintype "bidirectional"))
    )
    (net (code "83") (name "unconnected-(IC3E-PB4-Pad40)") (class "Default")
      (node (ref "IC3") (pin "40") (pinfunction "PB4_40") (pintype "bidirectional"))
    )
    (net (code "84") (name "unconnected-(IC3F-PC13-Pad2)") (class "Default")
      (node (ref "IC3") (pin "2") (pinfunction "PC13_2") (pintype "bidirectional"))
    )
    (net (code "85") (name "unconnected-(IC3F-PC14-Pad3)") (class "Default")
      (node (ref "IC3") (pin "3") (pinfunction "PC14_3") (pintype "bidirectional"))
    )
    (net (code "86") (name "unconnected-(IC3F-PC15-Pad4)") (class "Default")
      (node (ref "IC3") (pin "4") (pinfunction "PC15_4") (pintype "bidirectional"))
    )
    (net (code "87") (name "unconnected-(POWER-O-Pad1)") (class "Default")
      (node (ref "POWER") (pin "1") (pinfunction "O_1") (pintype "passive"))
    )
  )
)
